# Encoder.net
KiCad netlist of a schematic drawn in Altium Designer
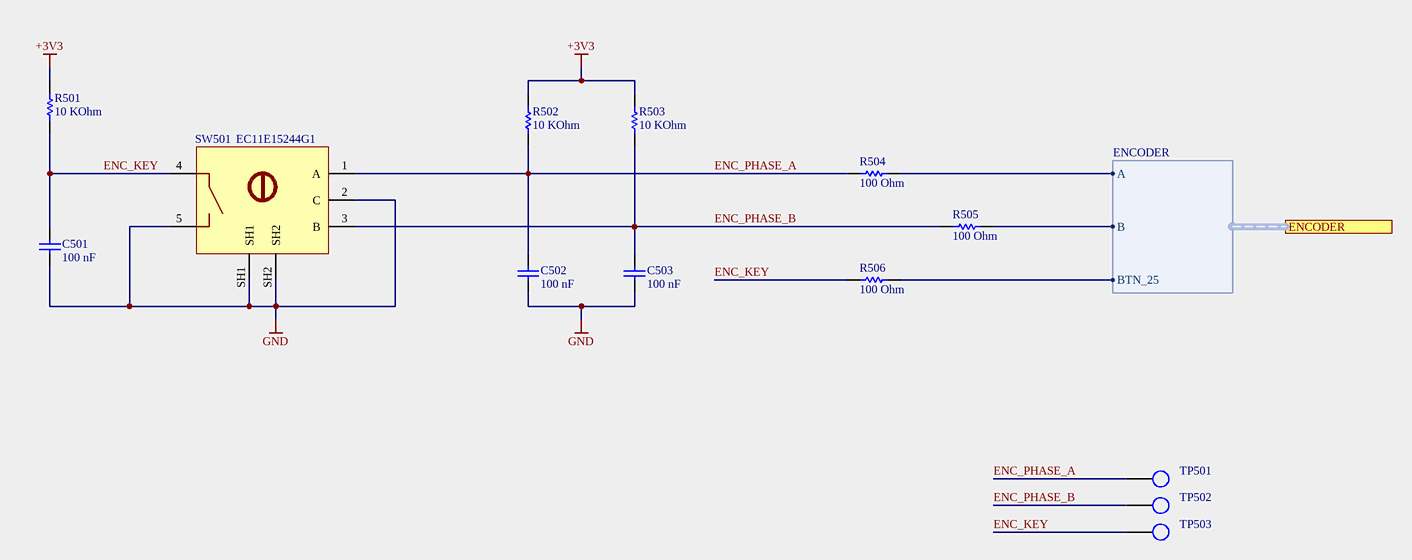
[diagram p0: Encoder.SchDoc]

(export (version "E")
  (design (tool "Eeschema 10.0.6"))
  (components
    (comp (ref "C501")
      (value "CAP-100N")
      (footprint "CAPC0603")
      (description "Chip Capacitor, 100 nF, +/- 5%")
      (fields (field (name "TOLERANCE") "5 %") (field (name "CAPACITANCE") "100 nF"))
      (libsource (lib "Конденсаторы керамические SMD") (part "CAP-100N"))
    )
    (comp (ref "C502")
      (value "CAP-100N")
      (footprint "CAPC0603")
      (description "Chip Capacitor, 100 nF, +/- 5%")
      (fields (field (name "TOLERANCE") "5 %") (field (name "CAPACITANCE") "100 nF"))
      (libsource (lib "Конденсаторы керамические SMD") (part "CAP-100N"))
    )
    (comp (ref "C503")
      (value "CAP-100N")
      (footprint "CAPC0603")
      (description "Chip Capacitor, 100 nF, +/- 5%")
      (fields (field (name "TOLERANCE") "5 %") (field (name "CAPACITANCE") "100 nF"))
      (libsource (lib "Конденсаторы керамические SMD") (part "CAP-100N"))
    )
    (comp (ref "R501")
      (value "RES-10K")
      (footprint "RES0603")
      (description "Chip Resistor, 10 KOhm, +/- 1%")
      (fields (field (name "TOLERANCE") "1 %") (field (name "RESISTANCE") "10 KOhm"))
      (libsource (lib "Резисторы SMD") (part "RES-10K"))
    )
    (comp (ref "R502")
      (value "RES-10K")
      (footprint "RES0603")
      (description "Chip Resistor, 10 KOhm, +/- 1%")
      (fields (field (name "TOLERANCE") "1 %") (field (name "RESISTANCE") "10 KOhm"))
      (libsource (lib "Резисторы SMD") (part "RES-10K"))
    )
    (comp (ref "R503")
      (value "RES-10K")
      (footprint "RES0603")
      (description "Chip Resistor, 10 KOhm, +/- 1%")
      (fields (field (name "TOLERANCE") "1 %") (field (name "RESISTANCE") "10 KOhm"))
      (libsource (lib "Резисторы SMD") (part "RES-10K"))
    )
    (comp (ref "R504")
      (value "RES-100")
      (footprint "RES0603")
      (description "Chip Resistor, 100 Ohm, +/- 1%")
      (fields (field (name "TOLERANCE") "1 %") (field (name "RESISTANCE") "100 Ohm"))
      (libsource (lib "Резисторы SMD") (part "RES-100"))
    )
    (comp (ref "R505")
      (value "RES-100")
      (footprint "RES0603")
      (description "Chip Resistor, 100 Ohm, +/- 1%")
      (fields (field (name "TOLERANCE") "1 %") (field (name "RESISTANCE") "100 Ohm"))
      (libsource (lib "Резисторы SMD") (part "RES-100"))
    )
    (comp (ref "R506")
      (value "RES-100")
      (footprint "RES0603")
      (description "Chip Resistor, 100 Ohm, +/- 1%")
      (fields (field (name "TOLERANCE") "1 %") (field (name "RESISTANCE") "100 Ohm"))
      (libsource (lib "Резисторы SMD") (part "RES-100"))
    )
    (comp (ref "SW501")
      (value "EC11E15244G1")
      (footprint "EC11E15244G1")
      (description "11mm Size Metal Shaft Type Encoder")
      (fields (field (name "PARTNUMBER") "EC11E15244G1"))
      (libsource (lib "Энкодеры") (part "EC11E15244G1"))
    )
    (comp (ref "TP501") (value "~") (footprint "TP_C-0.5mm") (libsource (lib "Разъемы") (part "TestPad")))
    (comp (ref "TP502") (value "~") (footprint "TP_C-0.5mm") (libsource (lib "Разъемы") (part "TestPad")))
    (comp (ref "TP503") (value "~") (footprint "TP_C-0.5mm") (libsource (lib "Разъемы") (part "TestPad")))
  )
  (nets
    (net (code "2") (name "+3V3") (class "Default")
      (node (ref "R501") (pin "2") (pinfunction "2_2") (pintype "passive"))
      (node (ref "R502") (pin "2") (pinfunction "2_2") (pintype "passive"))
      (node (ref "R503") (pin "2") (pinfunction "2_2") (pintype "passive"))
    )
    (net (code "3") (name "/A") (class "Default")
      (node (ref "R504") (pin "2") (pinfunction "2_2") (pintype "passive"))
    )
    (net (code "4") (name "/B") (class "Default")
      (node (ref "R505") (pin "2") (pinfunction "2_2") (pintype "passive"))
    )
    (net (code "5") (name "/BTN_25") (class "Default")
      (node (ref "R506") (pin "2") (pinfunction "2_2") (pintype "passive"))
    )
    (net (code "6") (name "/ENC_KEY") (class "Default")
      (node (ref "C501") (pin "2") (pinfunction "2_2") (pintype "passive"))
      (node (ref "R501") (pin "1") (pinfunction "1_1") (pintype "passive"))
      (node (ref "R506") (pin "1") (pinfunction "1_1") (pintype "passive"))
      (node (ref "SW501") (pin "4") (pintype "passive"))
      (node (ref "TP503") (pin "1") (pintype "passive"))
    )
    (net (code "7") (name "/ENC_PHASE_A") (class "Default")
      (node (ref "C502") (pin "2") (pinfunction "2_2") (pintype "passive"))
      (node (ref "R502") (pin "1") (pinfunction "1_1") (pintype "passive"))
      (node (ref "R504") (pin "1") (pinfunction "1_1") (pintype "passive"))
      (node (ref "SW501") (pin "1") (pinfunction "A_1") (pintype "passive"))
      (node (ref "TP501") (pin "1") (pintype "passive"))
    )
    (net (code "8") (name "/ENC_PHASE_B") (class "Default")
      (node (ref "C503") (pin "2") (pinfunction "2_2") (pintype "passive"))
      (node (ref "R503") (pin "1") (pinfunction "1_1") (pintype "passive"))
      (node (ref "R505") (pin "1") (pinfunction "1_1") (pintype "passive"))
      (node (ref "SW501") (pin "3") (pinfunction "B_3") (pintype "passive"))
      (node (ref "TP502") (pin "1") (pintype "passive"))
    )
    (net (code "10") (name "GND") (class "Default")
      (node (ref "C501") (pin "1") (pinfunction "1_1") (pintype "passive"))
      (node (ref "C502") (pin "1") (pinfunction "1_1") (pintype "passive"))
      (node (ref "C503") (pin "1") (pinfunction "1_1") (pintype "passive"))
      (node (ref "SW501") (pin "2") (pinfunction "C_2") (pintype "passive"))
      (node (ref "SW501") (pin "5") (pintype "passive"))
      (node (ref "SW501") (pin "SH1") (pinfunction "SH1_SH1") (pintype "passive"))
      (node (ref "SW501") (pin "SH2") (pinfunction "SH2_SH2") (pintype "passive"))
    )
  )
)
